# SwitchedATXBreakout.net
KiCad netlist of a schematic drawn in EAGLE
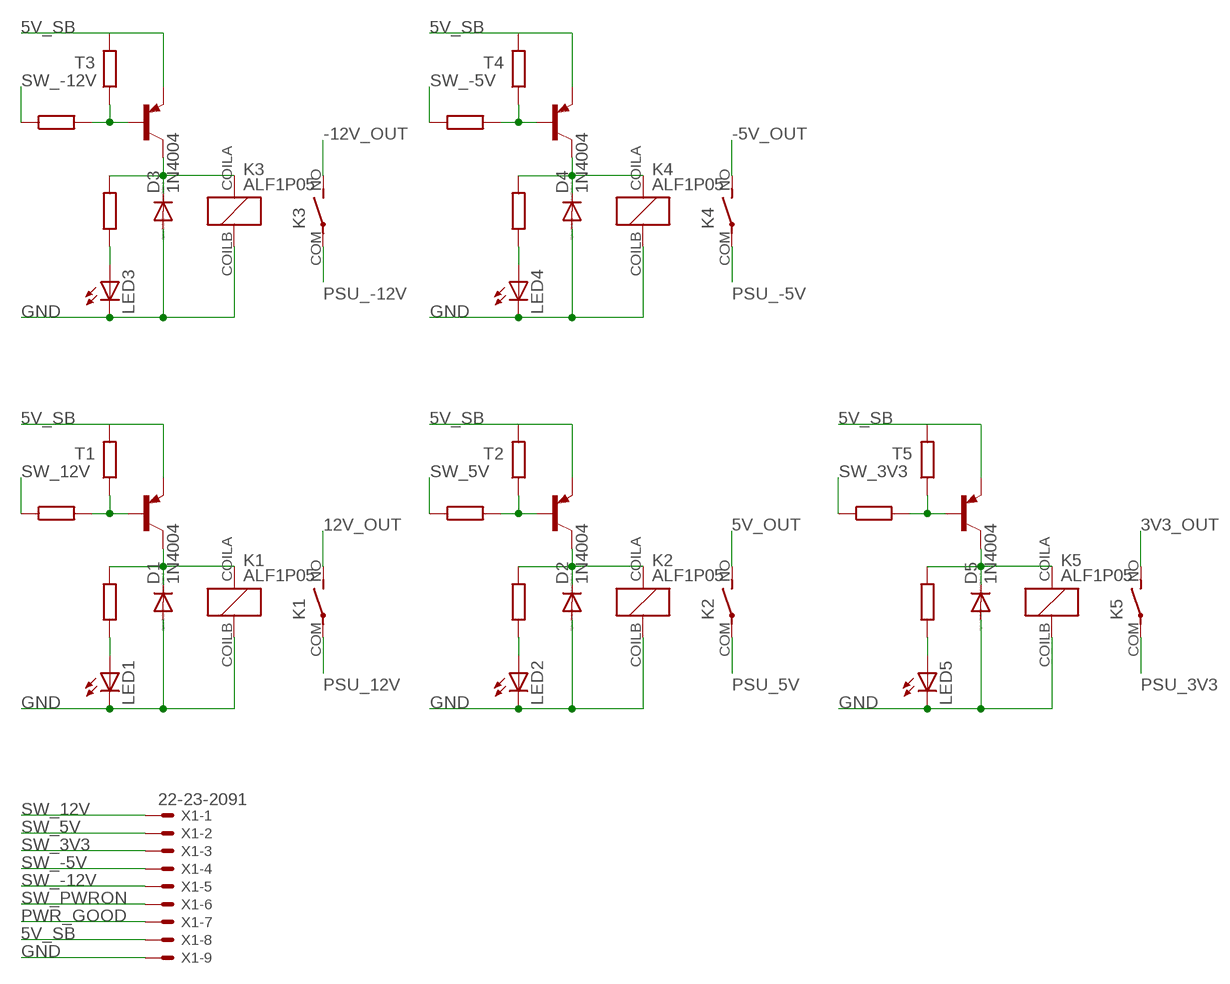
[diagram p0: schematic, sheet 1]

(export (version "E")
  (design (tool "Eeschema 10.0.6"))
  (components
    (comp (ref "D1")
      (value "1N4004")
      (footprint "eagle-import:DO41-10")
      (libsource (lib "eagle-import") (part "1N4004"))
    )
    (comp (ref "D2")
      (value "1N4004")
      (footprint "eagle-import:DO41-10")
      (libsource (lib "eagle-import") (part "1N4004"))
    )
    (comp (ref "D3")
      (value "1N4004")
      (footprint "eagle-import:DO41-10")
      (libsource (lib "eagle-import") (part "1N4004"))
    )
    (comp (ref "D4")
      (value "1N4004")
      (footprint "eagle-import:DO41-10")
      (libsource (lib "eagle-import") (part "1N4004"))
    )
    (comp (ref "D5")
      (value "1N4004")
      (footprint "eagle-import:DO41-10")
      (libsource (lib "eagle-import") (part "1N4004"))
    )
    (comp (ref "K1")
      (value "ALF1P05")
      (footprint "eagle-import:ALF")
      (libsource (lib "eagle-import") (part "ALF1P05"))
    )
    (comp (ref "K2")
      (value "ALF1P05")
      (footprint "eagle-import:ALF")
      (libsource (lib "eagle-import") (part "ALF1P05"))
    )
    (comp (ref "K3")
      (value "ALF1P05")
      (footprint "eagle-import:ALF")
      (libsource (lib "eagle-import") (part "ALF1P05"))
    )
    (comp (ref "K4")
      (value "ALF1P05")
      (footprint "eagle-import:ALF")
      (libsource (lib "eagle-import") (part "ALF1P05"))
    )
    (comp (ref "K5")
      (value "ALF1P05")
      (footprint "eagle-import:ALF")
      (libsource (lib "eagle-import") (part "ALF1P05"))
    )
    (comp (ref "LED1")
      (value "LED5MM")
      (footprint "eagle-import:LED5MM")
      (libsource (lib "eagle-import") (part "LED5MM"))
    )
    (comp (ref "LED2")
      (value "LED5MM")
      (footprint "eagle-import:LED5MM")
      (libsource (lib "eagle-import") (part "LED5MM"))
    )
    (comp (ref "LED3")
      (value "LED5MM")
      (footprint "eagle-import:LED5MM")
      (libsource (lib "eagle-import") (part "LED5MM"))
    )
    (comp (ref "LED4")
      (value "LED5MM")
      (footprint "eagle-import:LED5MM")
      (libsource (lib "eagle-import") (part "LED5MM"))
    )
    (comp (ref "LED5")
      (value "LED5MM")
      (footprint "eagle-import:LED5MM")
      (libsource (lib "eagle-import") (part "LED5MM"))
    )
    (comp (ref "T1")
      (value "-PNP-TO92")
      (footprint "eagle-import:TO92")
      (libsource (lib "eagle-import") (part "-PNP-TO92"))
    )
    (comp (ref "T2")
      (value "-PNP-TO92")
      (footprint "eagle-import:TO92")
      (libsource (lib "eagle-import") (part "-PNP-TO92"))
    )
    (comp (ref "T3")
      (value "-PNP-TO92")
      (footprint "eagle-import:TO92")
      (libsource (lib "eagle-import") (part "-PNP-TO92"))
    )
    (comp (ref "T4")
      (value "-PNP-TO92")
      (footprint "eagle-import:TO92")
      (libsource (lib "eagle-import") (part "-PNP-TO92"))
    )
    (comp (ref "T5")
      (value "-PNP-TO92")
      (footprint "eagle-import:TO92")
      (libsource (lib "eagle-import") (part "-PNP-TO92"))
    )
    (comp (ref "X1")
      (value "22-23-2091")
      (footprint "eagle-import:22-23-2091")
      (fields (field (name "MF") "MOLEX"))
      (libsource (lib "eagle-import") (part "22-23-2091"))
    )
  )
  (nets
    (net (code "1") (name "/-5V_OUT") (class "Default")
      (node (ref "K4") (pin "NO") (pinfunction "S_NO") (pintype "passive"))
    )
    (net (code "2") (name "/-12V_OUT") (class "Default")
      (node (ref "K3") (pin "NO") (pinfunction "S_NO") (pintype "passive"))
    )
    (net (code "3") (name "/3V3_OUT") (class "Default")
      (node (ref "K5") (pin "NO") (pinfunction "S_NO") (pintype "passive"))
    )
    (net (code "4") (name "/5V_OUT") (class "Default")
      (node (ref "K2") (pin "NO") (pinfunction "S_NO") (pintype "passive"))
    )
    (net (code "5") (name "/5V_SB") (class "Default")
      (node (ref "T1") (pin "1") (pinfunction "E_1") (pintype "passive"))
      (node (ref "T2") (pin "1") (pinfunction "E_1") (pintype "passive"))
      (node (ref "T3") (pin "1") (pinfunction "E_1") (pintype "passive"))
      (node (ref "T4") (pin "1") (pinfunction "E_1") (pintype "passive"))
      (node (ref "T5") (pin "1") (pinfunction "E_1") (pintype "passive"))
      (node (ref "X1") (pin "8") (pinfunction "S_8") (pintype "passive"))
    )
    (net (code "6") (name "/12V_OUT") (class "Default")
      (node (ref "K1") (pin "NO") (pinfunction "S_NO") (pintype "passive"))
    )
    (net (code "7") (name "/GND") (class "Default")
      (node (ref "D1") (pin "A") (pinfunction "A_A") (pintype "passive"))
      (node (ref "D2") (pin "A") (pinfunction "A_A") (pintype "passive"))
      (node (ref "D3") (pin "A") (pinfunction "A_A") (pintype "passive"))
      (node (ref "D4") (pin "A") (pinfunction "A_A") (pintype "passive"))
      (node (ref "D5") (pin "A") (pinfunction "A_A") (pintype "passive"))
      (node (ref "K1") (pin "COILB") (pinfunction "2_COILB") (pintype "passive"))
      (node (ref "K2") (pin "COILB") (pinfunction "2_COILB") (pintype "passive"))
      (node (ref "K3") (pin "COILB") (pinfunction "2_COILB") (pintype "passive"))
      (node (ref "K4") (pin "COILB") (pinfunction "2_COILB") (pintype "passive"))
      (node (ref "K5") (pin "COILB") (pinfunction "2_COILB") (pintype "passive"))
      (node (ref "LED1") (pin "K") (pinfunction "C_K") (pintype "passive"))
      (node (ref "LED2") (pin "K") (pinfunction "C_K") (pintype "passive"))
      (node (ref "LED3") (pin "K") (pinfunction "C_K") (pintype "passive"))
      (node (ref "LED4") (pin "K") (pinfunction "C_K") (pintype "passive"))
      (node (ref "LED5") (pin "K") (pinfunction "C_K") (pintype "passive"))
      (node (ref "X1") (pin "9") (pinfunction "S_9") (pintype "passive"))
    )
    (net (code "8") (name "/PSU_-5V") (class "Default")
      (node (ref "K4") (pin "COM") (pinfunction "P_COM") (pintype "passive"))
    )
    (net (code "9") (name "/PSU_-12V") (class "Default")
      (node (ref "K3") (pin "COM") (pinfunction "P_COM") (pintype "passive"))
    )
    (net (code "10") (name "/PSU_3V3") (class "Default")
      (node (ref "K5") (pin "COM") (pinfunction "P_COM") (pintype "passive"))
    )
    (net (code "11") (name "/PSU_5V") (class "Default")
      (node (ref "K2") (pin "COM") (pinfunction "P_COM") (pintype "passive"))
    )
    (net (code "12") (name "/PSU_12V") (class "Default")
      (node (ref "K1") (pin "COM") (pinfunction "P_COM") (pintype "passive"))
    )
    (net (code "13") (name "/PWR_GOOD") (class "Default")
      (node (ref "X1") (pin "7") (pinfunction "S_7") (pintype "passive"))
    )
    (net (code "14") (name "/SW_-5V") (class "Default")
      (node (ref "X1") (pin "4") (pinfunction "S_4") (pintype "passive"))
    )
    (net (code "15") (name "/SW_-12V") (class "Default")
      (node (ref "X1") (pin "5") (pinfunction "S_5") (pintype "passive"))
    )
    (net (code "16") (name "/SW_3V3") (class "Default")
      (node (ref "X1") (pin "3") (pinfunction "S_3") (pintype "passive"))
    )
    (net (code "17") (name "/SW_5V") (class "Default")
      (node (ref "X1") (pin "2") (pinfunction "S_2") (pintype "passive"))
    )
    (net (code "18") (name "/SW_12V") (class "Default")
      (node (ref "X1") (pin "1") (pinfunction "S_1") (pintype "passive"))
    )
    (net (code "19") (name "/SW_PWRON") (class "Default")
      (node (ref "X1") (pin "6") (pinfunction "S_6") (pintype "passive"))
    )
    (net (code "20") (name "Net-(K1B-1)") (class "Default")
      (node (ref "D1") (pin "C") (pinfunction "C_C") (pintype "passive"))
      (node (ref "K1") (pin "COILA") (pinfunction "1_COILA") (pintype "passive"))
      (node (ref "T1") (pin "3") (pinfunction "C_3") (pintype "passive"))
    )
    (net (code "21") (name "Net-(K2B-1)") (class "Default")
      (node (ref "D2") (pin "C") (pinfunction "C_C") (pintype "passive"))
      (node (ref "K2") (pin "COILA") (pinfunction "1_COILA") (pintype "passive"))
      (node (ref "T2") (pin "3") (pinfunction "C_3") (pintype "passive"))
    )
    (net (code "22") (name "Net-(K3B-1)") (class "Default")
      (node (ref "D3") (pin "C") (pinfunction "C_C") (pintype "passive"))
      (node (ref "K3") (pin "COILA") (pinfunction "1_COILA") (pintype "passive"))
      (node (ref "T3") (pin "3") (pinfunction "C_3") (pintype "passive"))
    )
    (net (code "23") (name "Net-(K4B-1)") (class "Default")
      (node (ref "D4") (pin "C") (pinfunction "C_C") (pintype "passive"))
      (node (ref "K4") (pin "COILA") (pinfunction "1_COILA") (pintype "passive"))
      (node (ref "T4") (pin "3") (pinfunction "C_3") (pintype "passive"))
    )
    (net (code "24") (name "Net-(K5B-1)") (class "Default")
      (node (ref "D5") (pin "C") (pinfunction "C_C") (pintype "passive"))
      (node (ref "K5") (pin "COILA") (pinfunction "1_COILA") (pintype "passive"))
      (node (ref "T5") (pin "3") (pinfunction "C_3") (pintype "passive"))
    )
    (net (code "25") (name "unconnected-(LED1-PadA)") (class "Default")
      (node (ref "LED1") (pin "A") (pinfunction "A_A") (pintype "passive"))
    )
    (net (code "26") (name "unconnected-(LED2-PadA)") (class "Default")
      (node (ref "LED2") (pin "A") (pinfunction "A_A") (pintype "passive"))
    )
    (net (code "27") (name "unconnected-(LED3-PadA)") (class "Default")
      (node (ref "LED3") (pin "A") (pinfunction "A_A") (pintype "passive"))
    )
    (net (code "28") (name "unconnected-(LED4-PadA)") (class "Default")
      (node (ref "LED4") (pin "A") (pinfunction "A_A") (pintype "passive"))
    )
    (net (code "29") (name "unconnected-(LED5-PadA)") (class "Default")
      (node (ref "LED5") (pin "A") (pinfunction "A_A") (pintype "passive"))
    )
    (net (code "30") (name "unconnected-(T1-B-Pad2)") (class "Default")
      (node (ref "T1") (pin "2") (pinfunction "B_2") (pintype "passive"))
    )
    (net (code "31") (name "unconnected-(T2-B-Pad2)") (class "Default")
      (node (ref "T2") (pin "2") (pinfunction "B_2") (pintype "passive"))
    )
    (net (code "32") (name "unconnected-(T3-B-Pad2)") (class "Default")
      (node (ref "T3") (pin "2") (pinfunction "B_2") (pintype "passive"))
    )
    (net (code "33") (name "unconnected-(T4-B-Pad2)") (class "Default")
      (node (ref "T4") (pin "2") (pinfunction "B_2") (pintype "passive"))
    )
    (net (code "34") (name "unconnected-(T5-B-Pad2)") (class "Default")
      (node (ref "T5") (pin "2") (pinfunction "B_2") (pintype "passive"))
    )
  )
)
